# I6ABreakout.net
KiCad netlist of a schematic drawn in EAGLE
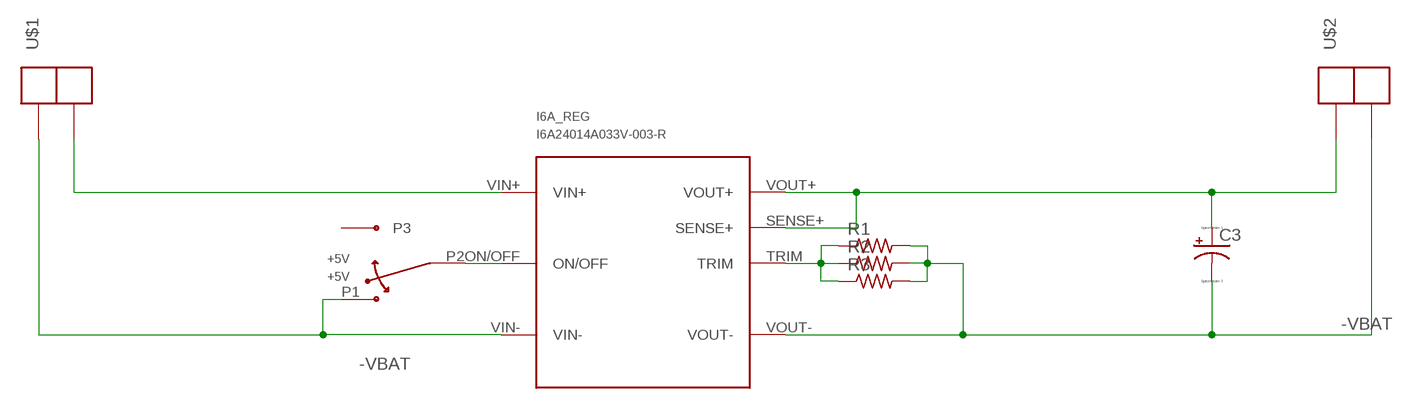
[diagram p0: schematic, sheet 1]

(export (version "E")
  (design (tool "Eeschema 10.0.6"))
  (components
    (comp (ref "+5V")
      (value "+5V")
      (footprint "eagle-import:SPDT-TOGGLE")
      (libsource (lib "eagle-import") (part "SPDT-TOGGLE"))
    )
    (comp (ref "C3")
      (value "CPOL-USD/7343-31R")
      (footprint "eagle-import:D_7343-31R")
      (libsource (lib "eagle-import") (part "CPOL-USD/7343-31R"))
    )
    (comp (ref "I6A_REG")
      (value "I6A24014A033V-003-R")
      (footprint "eagle-import:I6A")
      (libsource (lib "eagle-import") (part "I6A"))
    )
    (comp (ref "R1")
      (value "R-US_M0805")
      (footprint "eagle-import:M0805")
      (libsource (lib "eagle-import") (part "R-US_M0805"))
    )
    (comp (ref "R2")
      (value "R-US_M0805")
      (footprint "eagle-import:M0805")
      (libsource (lib "eagle-import") (part "R-US_M0805"))
    )
    (comp (ref "R3")
      (value "R-US_M0805")
      (footprint "eagle-import:M0805")
      (libsource (lib "eagle-import") (part "R-US_M0805"))
    )
    (comp (ref "U$1")
      (value "2PIN-HEADERANDERSON_RIGHTANGLE")
      (footprint "eagle-import:ANDERSON_RIGHTANGLE_X2")
      (libsource (lib "eagle-import") (part "2PIN-HEADERANDERSON_RIGHTANGLE"))
    )
    (comp (ref "U$2")
      (value "2PIN-HEADERANDERSON_RIGHTANGLE")
      (footprint "eagle-import:ANDERSON_RIGHTANGLE_X2")
      (libsource (lib "eagle-import") (part "2PIN-HEADERANDERSON_RIGHTANGLE"))
    )
  )
  (nets
    (net (code "1") (name "/-VBAT") (class "Default")
      (node (ref "+5V") (pin "P1") (pinfunction "P1_P1") (pintype "passive"))
      (node (ref "C3") (pin "-") (pinfunction "-_-") (pintype "passive"))
      (node (ref "I6A_REG") (pin "VIN-") (pinfunction "VIN-_VIN-") (pintype "bidirectional"))
      (node (ref "I6A_REG") (pin "VOUT-") (pinfunction "VOUT-_VOUT-") (pintype "bidirectional"))
      (node (ref "R1") (pin "2") (pinfunction "2_2") (pintype "passive"))
      (node (ref "R2") (pin "2") (pinfunction "2_2") (pintype "passive"))
      (node (ref "R3") (pin "2") (pinfunction "2_2") (pintype "passive"))
      (node (ref "U$1") (pin "P1") (pinfunction "P$1_P1") (pintype "bidirectional"))
      (node (ref "U$2") (pin "P2") (pinfunction "P$2_P2") (pintype "bidirectional"))
    )
    (net (code "2") (name "Net-(+5V-PadP2)") (class "Default")
      (node (ref "+5V") (pin "P2") (pinfunction "P2_P2") (pintype "passive"))
      (node (ref "I6A_REG") (pin "ON/OFF") (pinfunction "ON/OFF_ON/OFF") (pintype "bidirectional"))
    )
    (net (code "3") (name "Net-(I6A_REG-PadTRIM)") (class "Default")
      (node (ref "I6A_REG") (pin "TRIM") (pinfunction "TRIM_TRIM") (pintype "bidirectional"))
      (node (ref "R1") (pin "1") (pinfunction "1_1") (pintype "passive"))
      (node (ref "R2") (pin "1") (pinfunction "1_1") (pintype "passive"))
      (node (ref "R3") (pin "1") (pinfunction "1_1") (pintype "passive"))
    )
    (net (code "4") (name "Net-(U$1-P$2)") (class "Default")
      (node (ref "I6A_REG") (pin "VIN+") (pinfunction "VIN+_VIN+") (pintype "bidirectional"))
      (node (ref "U$1") (pin "P2") (pinfunction "P$2_P2") (pintype "bidirectional"))
    )
    (net (code "5") (name "Net-(U$2-P$1)") (class "Default")
      (node (ref "C3") (pin "+") (pinfunction "+_+") (pintype "passive"))
      (node (ref "I6A_REG") (pin "SENSE+") (pinfunction "SENSE+_SENSE+") (pintype "bidirectional"))
      (node (ref "I6A_REG") (pin "VOUT+") (pinfunction "VOUT+_VOUT+") (pintype "bidirectional"))
      (node (ref "U$2") (pin "P1") (pinfunction "P$1_P1") (pintype "bidirectional"))
    )
    (net (code "6") (name "unconnected-(+5V-PadP3)") (class "Default")
      (node (ref "+5V") (pin "P3") (pinfunction "P3_P3") (pintype "passive"))
    )
  )
)
